# BAT_VOLTAGE_SENS.net
KiCad netlist of a schematic drawn in Altium Designer
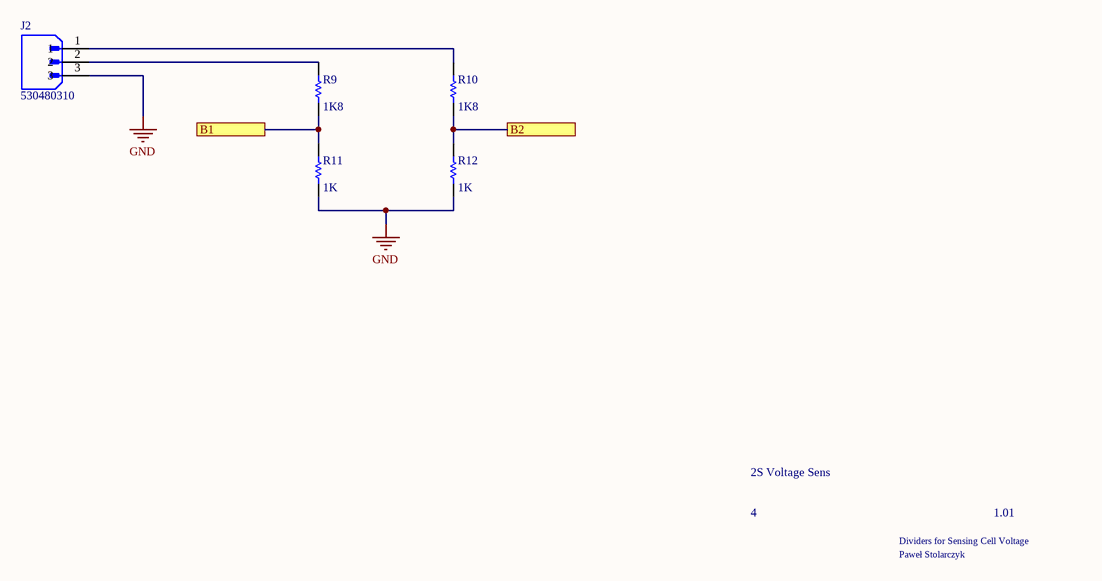
[diagram p0: BAT_VOLTAGE_SENS.SchDoc]

(export (version "E")
  (design (tool "Eeschema 10.0.6"))
  (components
    (comp (ref "J2")
      (value "530480310")
      (footprint "MOLEX_530480310")
      (libsource (lib "530480310") (part "530480310"))
    )
    (comp (ref "R9")
      (value "1K8")
      (footprint "0402")
      (description "Resistor")
      (fields (field (name "Comment") "Res1") (field (name "PUBLISHER") "Altium Limited"))
      (libsource (lib "Miscellaneous Devices") (part "Res1"))
    )
    (comp (ref "R10")
      (value "1K8")
      (footprint "0402")
      (description "Resistor")
      (fields (field (name "Comment") "Res1") (field (name "PUBLISHER") "Altium Limited"))
      (libsource (lib "Miscellaneous Devices") (part "Res1"))
    )
    (comp (ref "R11")
      (value "1K")
      (footprint "0402")
      (description "Resistor")
      (fields (field (name "Comment") "Res1") (field (name "PUBLISHER") "Altium Limited"))
      (libsource (lib "Miscellaneous Devices") (part "Res1"))
    )
    (comp (ref "R12")
      (value "1K")
      (footprint "0402")
      (description "Resistor")
      (fields (field (name "Comment") "Res1") (field (name "PUBLISHER") "Altium Limited"))
      (libsource (lib "Miscellaneous Devices") (part "Res1"))
    )
  )
  (nets
    (net (code "1") (name "/B1") (class "Default")
      (node (ref "R11") (pin "2") (pinfunction "2_2") (pintype "passive"))
      (node (ref "R9") (pin "1") (pinfunction "1_1") (pintype "passive"))
    )
    (net (code "2") (name "/B2") (class "Default")
      (node (ref "R10") (pin "1") (pinfunction "1_1") (pintype "passive"))
      (node (ref "R12") (pin "2") (pinfunction "2_2") (pintype "passive"))
    )
    (net (code "3") (name "GND") (class "Default")
      (node (ref "J2") (pin "3") (pinfunction "3_3") (pintype "passive"))
      (node (ref "R11") (pin "1") (pinfunction "1_1") (pintype "passive"))
      (node (ref "R12") (pin "1") (pinfunction "1_1") (pintype "passive"))
    )
    (net (code "4") (name "Net-(J2-Pad1)") (class "Default")
      (node (ref "J2") (pin "1") (pinfunction "1_1") (pintype "passive"))
      (node (ref "R10") (pin "2") (pinfunction "2_2") (pintype "passive"))
    )
    (net (code "5") (name "Net-(J2-Pad2)") (class "Default")
      (node (ref "J2") (pin "2") (pinfunction "2_2") (pintype "passive"))
      (node (ref "R9") (pin "2") (pinfunction "2_2") (pintype "passive"))
    )
  )
)
